# sch.net
KiCad netlist of a schematic drawn in Altium Designer
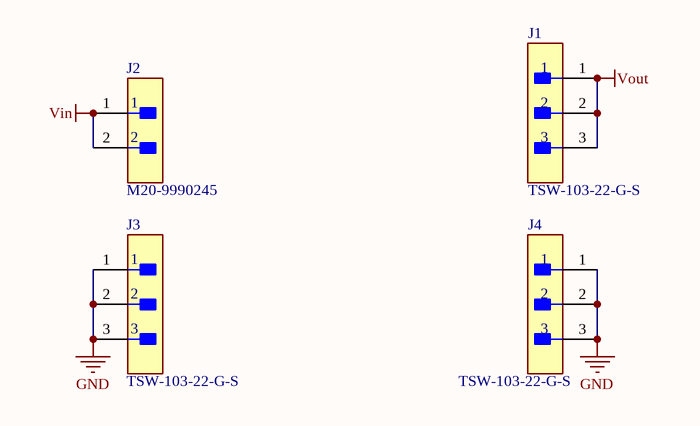
[diagram p0: sch.SchDoc]

(export (version "E")
  (design (tool "Eeschema 10.0.6"))
  (components
    (comp (ref "J1")
      (value "TSW-103-22-G-S")
      (footprint "FP-TSW-103-22-G-S-MFG")
      (description "Conn Unshrouded Header HDR 3 POS 2.54mm Solder ST Thru-Hole Bulk")
      (libsource (lib "Altium Content Vault") (part "0d3f023dd272f625e17a2be33dea85f"))
    )
    (comp (ref "J2")
      (value "M20-9990245")
      (footprint "FP-M20-9990245-MFG")
      (description "CONN HEADER VERT 2POS 2.54MM")
      (fields (field (name "VOLTAGE") "50V"))
      (libsource (lib "Altium Content Vault") (part "3bc925449376181038e59eaffc5286c"))
    )
    (comp (ref "J3")
      (value "TSW-103-22-G-S")
      (footprint "FP-TSW-103-22-G-S-MFG")
      (description "Conn Unshrouded Header HDR 3 POS 2.54mm Solder ST Thru-Hole Bulk")
      (libsource (lib "") (part "0d3f023dd272f625e17a2be33dea85f_1"))
    )
    (comp (ref "J4")
      (value "TSW-103-22-G-S")
      (footprint "FP-TSW-103-22-G-S-MFG")
      (description "Conn Unshrouded Header HDR 3 POS 2.54mm Solder ST Thru-Hole Bulk")
      (libsource (lib "Altium Content Vault") (part "0d3f023dd272f625e17a2be33dea85f"))
    )
  )
  (nets
    (net (code "1") (name "GND") (class "Default")
      (node (ref "J3") (pin "1") (pinfunction "1_1") (pintype "passive"))
      (node (ref "J3") (pin "2") (pinfunction "2_2") (pintype "passive"))
      (node (ref "J3") (pin "3") (pinfunction "3_3") (pintype "passive"))
      (node (ref "J4") (pin "1") (pinfunction "1_1") (pintype "passive"))
      (node (ref "J4") (pin "2") (pinfunction "2_2") (pintype "passive"))
      (node (ref "J4") (pin "3") (pinfunction "3_3") (pintype "passive"))
    )
    (net (code "2") (name "Vin") (class "Default")
      (node (ref "J2") (pin "1") (pinfunction "1_1") (pintype "passive"))
      (node (ref "J2") (pin "2") (pinfunction "2_2") (pintype "passive"))
    )
    (net (code "3") (name "Vout") (class "Default")
      (node (ref "J1") (pin "1") (pinfunction "1_1") (pintype "passive"))
      (node (ref "J1") (pin "2") (pinfunction "2_2") (pintype "passive"))
      (node (ref "J1") (pin "3") (pinfunction "3_3") (pintype "passive"))
    )
  )
)
